# placa1.net
KiCad netlist of a schematic drawn in EAGLE
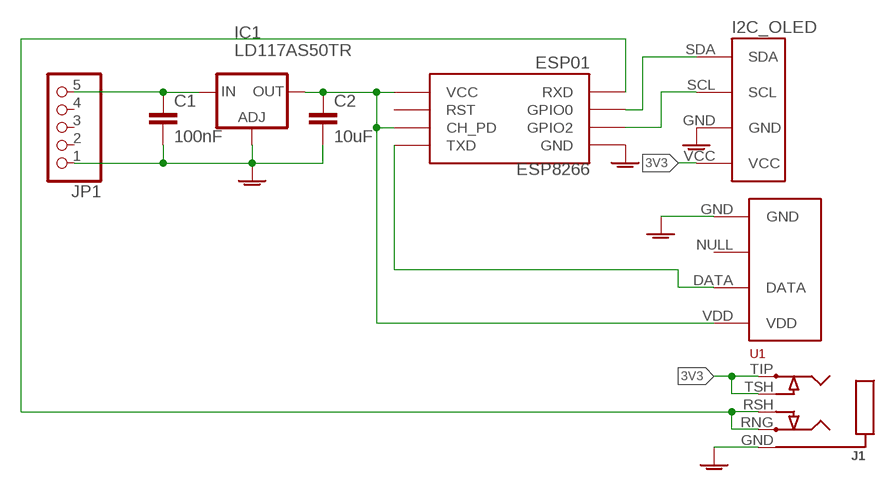
[diagram p0: schematic, sheet 1]

(export (version "E")
  (design (tool "Eeschema 10.0.6"))
  (components
    (comp (ref "C1")
      (value "100nF")
      (footprint "eagle-import:C1206K")
      (libsource (lib "eagle-import") (part "C-EUC1206K"))
    )
    (comp (ref "C2")
      (value "10uF")
      (footprint "eagle-import:C1206K")
      (libsource (lib "eagle-import") (part "C-EUC1206K"))
    )
    (comp (ref "ESP8266")
      (value "ESP01")
      (footprint "eagle-import:ESP01")
      (libsource (lib "eagle-import") (part "ESP01"))
    )
    (comp (ref "IC1")
      (value "LD117AS50TR")
      (footprint "eagle-import:SOT223")
      (libsource (lib "eagle-import") (part "LD117A?S50TR"))
    )
    (comp (ref "J1")
      (value "STEREOJACKSJ1-352XNG")
      (footprint "eagle-import:SJ1-352XNG")
      (libsource (lib "eagle-import") (part "STEREOJACKSJ1-352XNG"))
    )
    (comp (ref "JP1")
      (value "PINHD-1X5")
      (footprint "eagle-import:1X05")
      (libsource (lib "eagle-import") (part "PINHD-1X5"))
    )
    (comp (ref "OLED")
      (value "I2C_OLED")
      (footprint "eagle-import:I2C_OLED_PACKAGE")
      (libsource (lib "eagle-import") (part "I2C_OLED"))
    )
    (comp (ref "U1")
      (value "RHT03_DHT-22_AM2302RA")
      (footprint "eagle-import:RHT03_DHT-22_RA")
      (libsource (lib "eagle-import") (part "RHT03_DHT-22_AM2302RA"))
    )
  )
  (nets
    (net (code "1") (name "3V3") (class "Default")
      (node (ref "C2") (pin "1") (pinfunction "1_1") (pintype "passive"))
      (node (ref "ESP8266") (pin "CH_PD") (pinfunction "CH_PD_CH_PD") (pintype "bidirectional"))
      (node (ref "ESP8266") (pin "VCC") (pinfunction "VCC_VCC") (pintype "bidirectional"))
      (node (ref "IC1") (pin "2") (pinfunction "OUT_2") (pintype "passive"))
      (node (ref "J1") (pin "TIP") (pinfunction "TIP_TIP") (pintype "passive"))
      (node (ref "J1") (pin "TSH") (pinfunction "TSH_TSH") (pintype "passive"))
      (node (ref "OLED") (pin "VCC") (pinfunction "VCC_VCC") (pintype "bidirectional"))
      (node (ref "U1") (pin "VDD") (pinfunction "VDD_VDD") (pintype "power_in"))
    )
    (net (code "2") (name "GNDA") (class "Default")
      (node (ref "C1") (pin "2") (pinfunction "2_2") (pintype "passive"))
      (node (ref "C2") (pin "2") (pinfunction "2_2") (pintype "passive"))
      (node (ref "ESP8266") (pin "GND") (pinfunction "GND_GND") (pintype "bidirectional"))
      (node (ref "IC1") (pin "1") (pinfunction "ADJ_1") (pintype "input"))
      (node (ref "J1") (pin "GND") (pinfunction "GND_GND") (pintype "passive"))
      (node (ref "JP1") (pin "1") (pinfunction "1_1") (pintype "passive"))
      (node (ref "OLED") (pin "GND") (pinfunction "GND_GND") (pintype "bidirectional"))
      (node (ref "U1") (pin "GND") (pinfunction "GND_GND") (pintype "power_in"))
    )
    (net (code "3") (name "Net-(ESP8266-PadGPIO0)") (class "Default")
      (node (ref "ESP8266") (pin "GPIO0") (pinfunction "GPIO0_GPIO0") (pintype "bidirectional"))
      (node (ref "OLED") (pin "SDA") (pinfunction "SDA_SDA") (pintype "bidirectional"))
    )
    (net (code "4") (name "Net-(ESP8266-PadGPIO2)") (class "Default")
      (node (ref "ESP8266") (pin "GPIO2") (pinfunction "GPIO2_GPIO2") (pintype "bidirectional"))
      (node (ref "OLED") (pin "SCL") (pinfunction "SCL_SCL") (pintype "bidirectional"))
    )
    (net (code "5") (name "Net-(ESP8266-RXD)") (class "Default")
      (node (ref "ESP8266") (pin "RX") (pinfunction "RXD_RX") (pintype "bidirectional"))
      (node (ref "J1") (pin "RNG") (pinfunction "RNG_RNG") (pintype "passive"))
      (node (ref "J1") (pin "RSH") (pinfunction "RSH_RSH") (pintype "passive"))
    )
    (net (code "6") (name "Net-(ESP8266-TXD)") (class "Default")
      (node (ref "ESP8266") (pin "TX") (pinfunction "TXD_TX") (pintype "bidirectional"))
      (node (ref "U1") (pin "DATA") (pinfunction "DATA_DATA") (pintype "bidirectional"))
    )
    (net (code "7") (name "Net-(IC1-IN)") (class "Default")
      (node (ref "C1") (pin "1") (pinfunction "1_1") (pintype "passive"))
      (node (ref "IC1") (pin "3") (pinfunction "IN_3") (pintype "input"))
      (node (ref "JP1") (pin "5") (pinfunction "5_5") (pintype "passive"))
    )
    (net (code "8") (name "unconnected-(ESP8266-PadRST)") (class "Default")
      (node (ref "ESP8266") (pin "RST") (pinfunction "RST_RST") (pintype "bidirectional"))
    )
    (net (code "9") (name "unconnected-(JP1-Pad2)") (class "Default")
      (node (ref "JP1") (pin "2") (pinfunction "2_2") (pintype "passive"))
    )
    (net (code "10") (name "unconnected-(JP1-Pad3)") (class "Default")
      (node (ref "JP1") (pin "3") (pinfunction "3_3") (pintype "passive"))
    )
    (net (code "11") (name "unconnected-(JP1-Pad4)") (class "Default")
      (node (ref "JP1") (pin "4") (pinfunction "4_4") (pintype "passive"))
    )
    (net (code "12") (name "unconnected-(U1-PadNULL)") (class "Default")
      (node (ref "U1") (pin "NULL") (pinfunction "NULL_NULL") (pintype "no_connect"))
    )
  )
)
